# PicoKbd.net
KiCad netlist of a schematic drawn in EAGLE
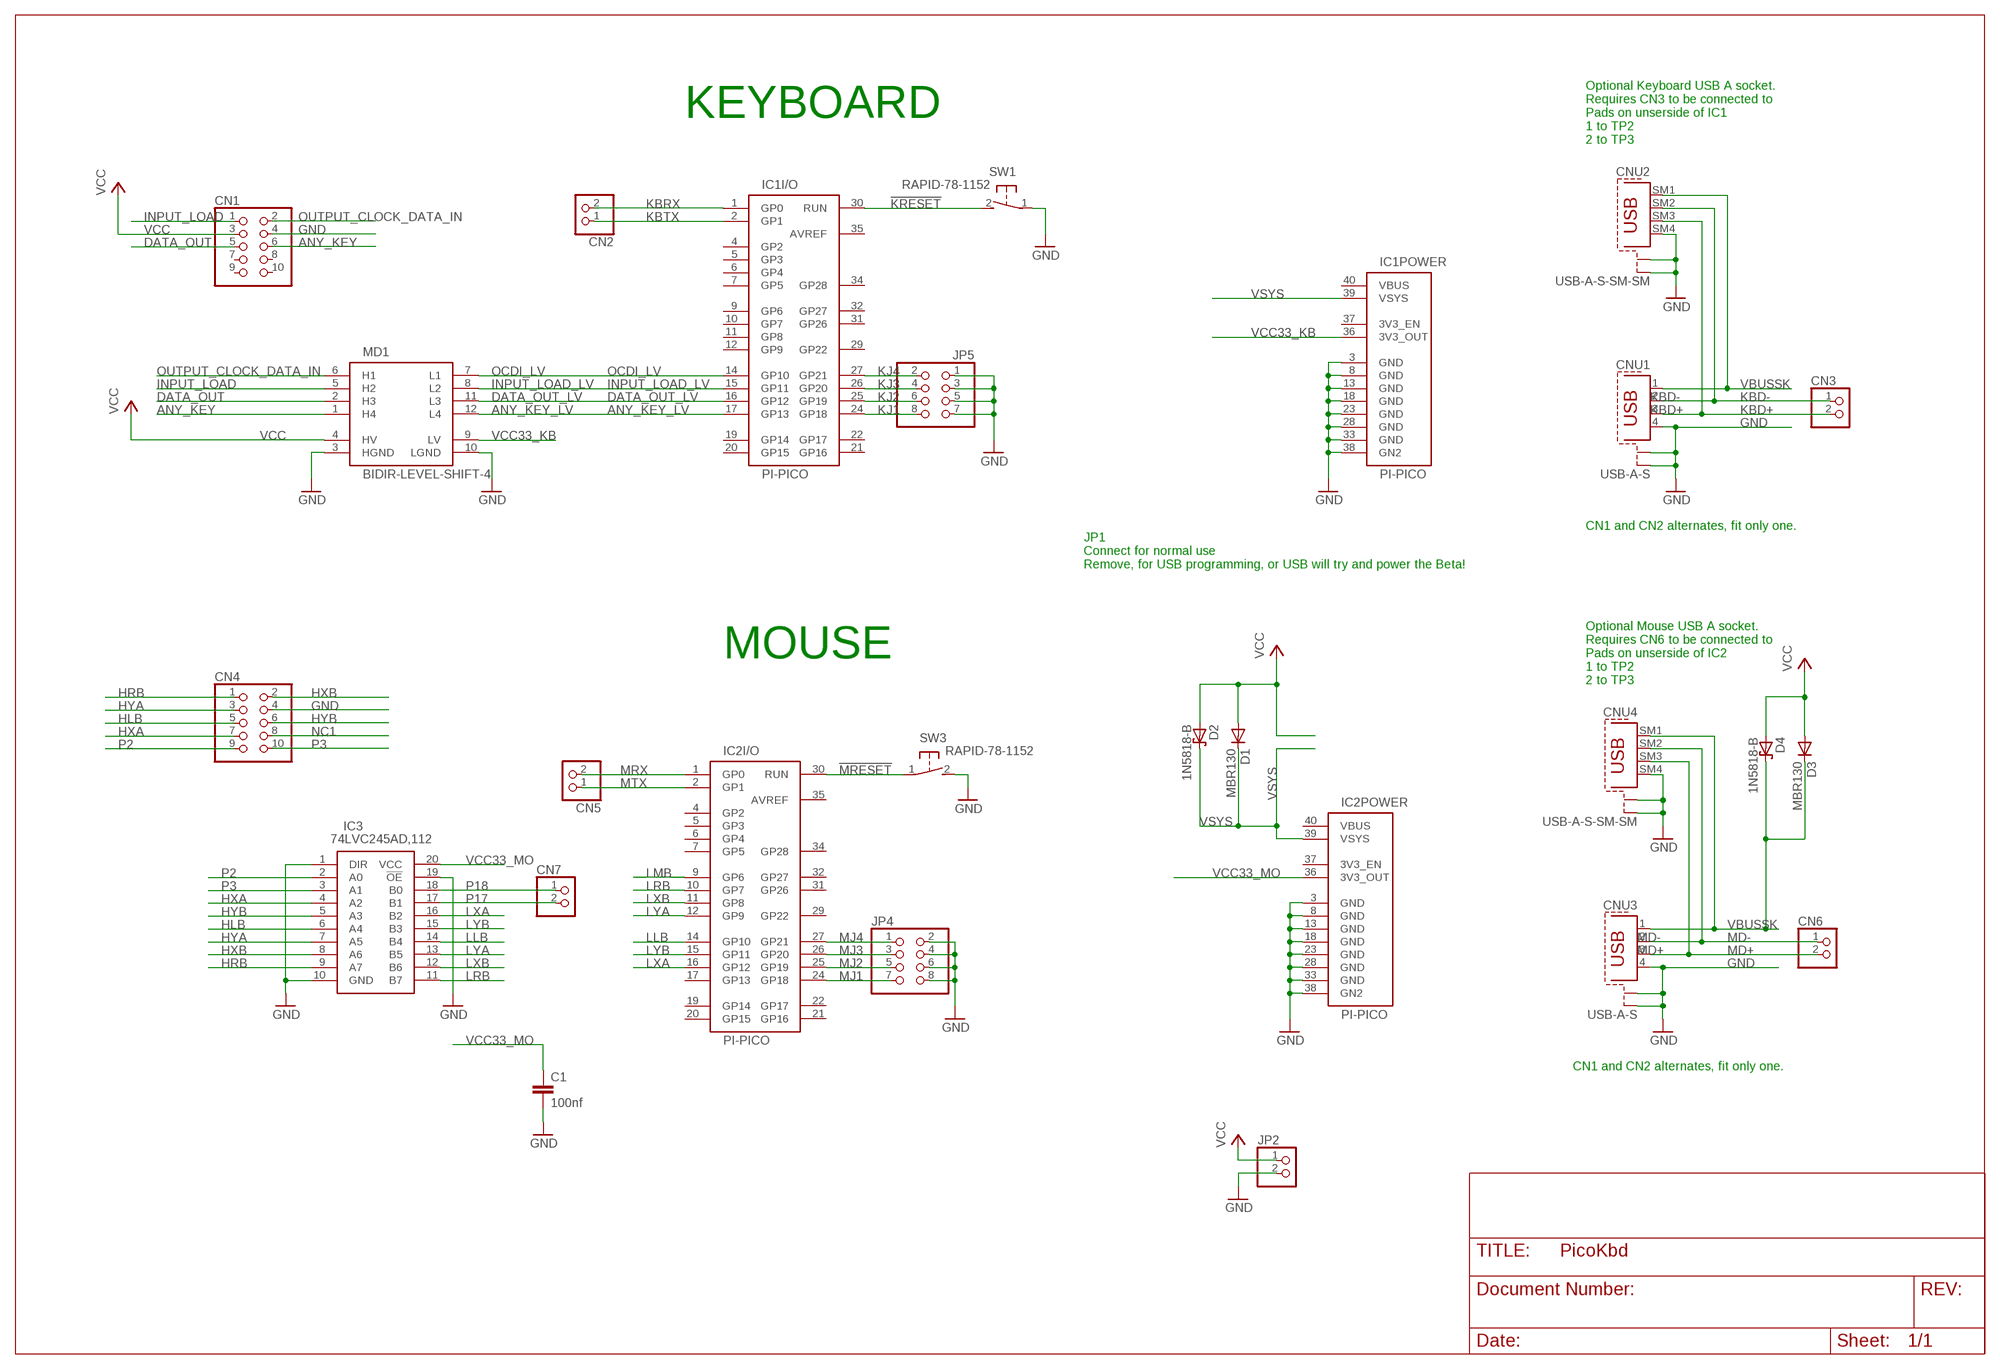
[diagram p0: schematic, sheet 1]

(export (version "E")
  (design (tool "Eeschema 10.0.6"))
  (components
    (comp (ref "C1")
      (value "100nf")
      (footprint "eagle-import:C025-025X050")
      (libsource (lib "eagle-import") (part "C-EU025-025X050"))
    )
    (comp (ref "CN1")
      (value "PINHD-2X5/90")
      (footprint "eagle-import:2X05_90")
      (libsource (lib "eagle-import") (part "PINHD-2X5/90"))
    )
    (comp (ref "CN2")
      (value "PINHD-1X2")
      (footprint "eagle-import:1X02")
      (libsource (lib "eagle-import") (part "PINHD-1X2"))
    )
    (comp (ref "CN3")
      (value "PINHD-1X2")
      (footprint "eagle-import:1X02")
      (libsource (lib "eagle-import") (part "PINHD-1X2"))
    )
    (comp (ref "CN4")
      (value "PINHD-2X5/90")
      (footprint "eagle-import:2X05_90")
      (libsource (lib "eagle-import") (part "PINHD-2X5/90"))
    )
    (comp (ref "CN5")
      (value "PINHD-1X2")
      (footprint "eagle-import:1X02")
      (libsource (lib "eagle-import") (part "PINHD-1X2"))
    )
    (comp (ref "CN6")
      (value "PINHD-1X2")
      (footprint "eagle-import:1X02")
      (libsource (lib "eagle-import") (part "PINHD-1X2"))
    )
    (comp (ref "CN7")
      (value "PINHD-1X2")
      (footprint "eagle-import:1X02")
      (libsource (lib "eagle-import") (part "PINHD-1X2"))
    )
    (comp (ref "CNU1")
      (value "USB-A-S")
      (footprint "eagle-import:USB-A-SHIELD-PTH")
      (libsource (lib "eagle-import") (part "USB-A-S"))
    )
    (comp (ref "CNU2")
      (value "USB-A-S-SM-SM")
      (footprint "eagle-import:USB-A-SHIELD-SM")
      (libsource (lib "eagle-import") (part "USB-A-S-SM-SM"))
    )
    (comp (ref "CNU3")
      (value "USB-A-S")
      (footprint "eagle-import:USB-A-SHIELD-PTH")
      (libsource (lib "eagle-import") (part "USB-A-S"))
    )
    (comp (ref "CNU4")
      (value "USB-A-S-SM-SM")
      (footprint "eagle-import:USB-A-SHIELD-SM")
      (libsource (lib "eagle-import") (part "USB-A-S-SM-SM"))
    )
    (comp (ref "D1")
      (value "MBR130")
      (footprint "eagle-import:SOD123")
      (libsource (lib "eagle-import") (part "MBR0520LT"))
    )
    (comp (ref "D2")
      (value "1N5818-B")
      (footprint "eagle-import:DO41-7.6")
      (libsource (lib "eagle-import") (part "1N5818-B"))
    )
    (comp (ref "D3")
      (value "MBR130")
      (footprint "eagle-import:SOD123")
      (libsource (lib "eagle-import") (part "MBR0520LT"))
    )
    (comp (ref "D4")
      (value "1N5818-B")
      (footprint "eagle-import:DO41-7.6")
      (libsource (lib "eagle-import") (part "1N5818-B"))
    )
    (comp (ref "IC1")
      (value "PI-PICO")
      (footprint "eagle-import:PI-PICO-MAIN")
      (libsource (lib "eagle-import") (part "PI-PICO"))
    )
    (comp (ref "IC2")
      (value "PI-PICO")
      (footprint "eagle-import:PI-PICO-MAIN")
      (libsource (lib "eagle-import") (part "PI-PICO"))
    )
    (comp (ref "IC3")
      (value "74LVC245AD,112")
      (footprint "eagle-import:SOIC127P1032X265-20N")
      (fields (field (name "RS_PART_NUMBER") "3800279P"))
      (libsource (lib "eagle-import") (part "74LVC245AD,112"))
    )
    (comp (ref "JP2")
      (value "PINHD-1X2/90")
      (footprint "eagle-import:1X02_90")
      (libsource (lib "eagle-import") (part "PINHD-1X2/90"))
    )
    (comp (ref "JP4")
      (value "PINHD-2X4")
      (footprint "eagle-import:2X04")
      (libsource (lib "eagle-import") (part "PINHD-2X4"))
    )
    (comp (ref "JP5")
      (value "PINHD-2X4")
      (footprint "eagle-import:2X04")
      (libsource (lib "eagle-import") (part "PINHD-2X4"))
    )
    (comp (ref "MD1")
      (value "BIDIR-LEVEL-SHIFT-4")
      (footprint "eagle-import:BIDIR-LEVEL-SHIFT")
      (libsource (lib "eagle-import") (part "BIDIR-LEVEL-SHIFT-4"))
    )
    (comp (ref "SW1")
      (value "RAPID-78-1152")
      (footprint "eagle-import:B3F-31XX")
      (libsource (lib "eagle-import") (part "RAPID-78-1152"))
    )
    (comp (ref "SW3")
      (value "RAPID-78-1152")
      (footprint "eagle-import:B3F-31XX")
      (libsource (lib "eagle-import") (part "RAPID-78-1152"))
    )
  )
  (nets
    (net (code "1") (name "/ANY_KEY") (class "Default")
      (node (ref "CN1") (pin "6") (pinfunction "6_6") (pintype "passive"))
      (node (ref "MD1") (pin "1") (pinfunction "H4_1") (pintype "passive"))
    )
    (net (code "2") (name "/ANY_KEY_LV") (class "Default")
      (node (ref "IC1") (pin "17") (pinfunction "GP13_17") (pintype "bidirectional"))
      (node (ref "MD1") (pin "12") (pinfunction "L4_12") (pintype "passive"))
    )
    (net (code "3") (name "/DATA_OUT") (class "Default")
      (node (ref "CN1") (pin "5") (pinfunction "5_5") (pintype "passive"))
      (node (ref "MD1") (pin "2") (pinfunction "H3_2") (pintype "passive"))
    )
    (net (code "4") (name "/DATA_OUT_LV") (class "Default")
      (node (ref "IC1") (pin "16") (pinfunction "GP12_16") (pintype "bidirectional"))
      (node (ref "MD1") (pin "11") (pinfunction "L3_11") (pintype "passive"))
    )
    (net (code "5") (name "/HLB") (class "Default")
      (node (ref "CN4") (pin "5") (pinfunction "5_5") (pintype "passive"))
      (node (ref "IC3") (pin "6") (pinfunction "A4_6") (pintype "bidirectional"))
    )
    (net (code "6") (name "/HRB") (class "Default")
      (node (ref "CN4") (pin "1") (pinfunction "1_1") (pintype "passive"))
      (node (ref "IC3") (pin "9") (pinfunction "A7_9") (pintype "bidirectional"))
    )
    (net (code "7") (name "/HXA") (class "Default")
      (node (ref "CN4") (pin "7") (pinfunction "7_7") (pintype "passive"))
      (node (ref "IC3") (pin "4") (pinfunction "A2_4") (pintype "bidirectional"))
    )
    (net (code "8") (name "/HXB") (class "Default")
      (node (ref "CN4") (pin "2") (pinfunction "2_2") (pintype "passive"))
      (node (ref "IC3") (pin "8") (pinfunction "A6_8") (pintype "bidirectional"))
    )
    (net (code "9") (name "/HYA") (class "Default")
      (node (ref "CN4") (pin "3") (pinfunction "3_3") (pintype "passive"))
      (node (ref "IC3") (pin "7") (pinfunction "A5_7") (pintype "bidirectional"))
    )
    (net (code "10") (name "/HYB") (class "Default")
      (node (ref "CN4") (pin "6") (pinfunction "6_6") (pintype "passive"))
      (node (ref "IC3") (pin "5") (pinfunction "A3_5") (pintype "bidirectional"))
    )
    (net (code "11") (name "/INPUT_LOAD") (class "Default")
      (node (ref "CN1") (pin "1") (pinfunction "1_1") (pintype "passive"))
      (node (ref "MD1") (pin "5") (pinfunction "H2_5") (pintype "passive"))
    )
    (net (code "12") (name "/INPUT_LOAD_LV") (class "Default")
      (node (ref "IC1") (pin "15") (pinfunction "GP11_15") (pintype "bidirectional"))
      (node (ref "MD1") (pin "8") (pinfunction "L2_8") (pintype "passive"))
    )
    (net (code "13") (name "/KBD+") (class "Default")
      (node (ref "CN3") (pin "2") (pinfunction "2_2") (pintype "passive"))
      (node (ref "CNU1") (pin "3") (pinfunction "3_3") (pintype "passive"))
      (node (ref "CNU2") (pin "SM3") (pinfunction "3_SM3") (pintype "passive"))
    )
    (net (code "14") (name "/KBD-") (class "Default")
      (node (ref "CN3") (pin "1") (pinfunction "1_1") (pintype "passive"))
      (node (ref "CNU1") (pin "2") (pinfunction "2_2") (pintype "passive"))
      (node (ref "CNU2") (pin "SM2") (pinfunction "2_SM2") (pintype "passive"))
    )
    (net (code "15") (name "/KBRX") (class "Default")
      (node (ref "CN2") (pin "2") (pinfunction "2_2") (pintype "passive"))
      (node (ref "IC1") (pin "1") (pinfunction "GP0_1") (pintype "bidirectional"))
    )
    (net (code "16") (name "/KBTX") (class "Default")
      (node (ref "CN2") (pin "1") (pinfunction "1_1") (pintype "passive"))
      (node (ref "IC1") (pin "2") (pinfunction "GP1_2") (pintype "bidirectional"))
    )
    (net (code "17") (name "/KJ1") (class "Default")
      (node (ref "IC1") (pin "24") (pinfunction "GP18_24") (pintype "bidirectional"))
      (node (ref "JP5") (pin "8") (pinfunction "8_8") (pintype "passive"))
    )
    (net (code "18") (name "/KJ2") (class "Default")
      (node (ref "IC1") (pin "25") (pinfunction "GP19_25") (pintype "bidirectional"))
      (node (ref "JP5") (pin "6") (pinfunction "6_6") (pintype "passive"))
    )
    (net (code "19") (name "/KJ3") (class "Default")
      (node (ref "IC1") (pin "26") (pinfunction "GP20_26") (pintype "bidirectional"))
      (node (ref "JP5") (pin "4") (pinfunction "4_4") (pintype "passive"))
    )
    (net (code "20") (name "/KJ4") (class "Default")
      (node (ref "IC1") (pin "27") (pinfunction "GP21_27") (pintype "bidirectional"))
      (node (ref "JP5") (pin "2") (pinfunction "2_2") (pintype "passive"))
    )
    (net (code "21") (name "/LLB") (class "Default")
      (node (ref "IC2") (pin "14") (pinfunction "GP10_14") (pintype "bidirectional"))
      (node (ref "IC3") (pin "14") (pinfunction "B4_14") (pintype "bidirectional"))
    )
    (net (code "22") (name "/LMB") (class "Default")
      (node (ref "IC2") (pin "9") (pinfunction "GP6_9") (pintype "bidirectional"))
    )
    (net (code "23") (name "/LRB") (class "Default")
      (node (ref "IC2") (pin "10") (pinfunction "GP7_10") (pintype "bidirectional"))
      (node (ref "IC3") (pin "11") (pinfunction "B7_11") (pintype "bidirectional"))
    )
    (net (code "24") (name "/LXA") (class "Default")
      (node (ref "IC2") (pin "16") (pinfunction "GP12_16") (pintype "bidirectional"))
      (node (ref "IC3") (pin "16") (pinfunction "B2_16") (pintype "bidirectional"))
    )
    (net (code "25") (name "/LXB") (class "Default")
      (node (ref "IC2") (pin "11") (pinfunction "GP8_11") (pintype "bidirectional"))
      (node (ref "IC3") (pin "12") (pinfunction "B6_12") (pintype "bidirectional"))
    )
    (net (code "26") (name "/LYA") (class "Default")
      (node (ref "IC2") (pin "12") (pinfunction "GP9_12") (pintype "bidirectional"))
      (node (ref "IC3") (pin "13") (pinfunction "B5_13") (pintype "bidirectional"))
    )
    (net (code "27") (name "/LYB") (class "Default")
      (node (ref "IC2") (pin "15") (pinfunction "GP11_15") (pintype "bidirectional"))
      (node (ref "IC3") (pin "15") (pinfunction "B3_15") (pintype "bidirectional"))
    )
    (net (code "28") (name "/MD+") (class "Default")
      (node (ref "CN6") (pin "2") (pinfunction "2_2") (pintype "passive"))
      (node (ref "CNU3") (pin "3") (pinfunction "3_3") (pintype "passive"))
      (node (ref "CNU4") (pin "SM3") (pinfunction "3_SM3") (pintype "passive"))
    )
    (net (code "29") (name "/MD-") (class "Default")
      (node (ref "CN6") (pin "1") (pinfunction "1_1") (pintype "passive"))
      (node (ref "CNU3") (pin "2") (pinfunction "2_2") (pintype "passive"))
      (node (ref "CNU4") (pin "SM2") (pinfunction "2_SM2") (pintype "passive"))
    )
    (net (code "30") (name "/MJ1") (class "Default")
      (node (ref "IC2") (pin "24") (pinfunction "GP18_24") (pintype "bidirectional"))
      (node (ref "JP4") (pin "7") (pinfunction "7_7") (pintype "passive"))
    )
    (net (code "31") (name "/MJ2") (class "Default")
      (node (ref "IC2") (pin "25") (pinfunction "GP19_25") (pintype "bidirectional"))
      (node (ref "JP4") (pin "5") (pinfunction "5_5") (pintype "passive"))
    )
    (net (code "32") (name "/MJ3") (class "Default")
      (node (ref "IC2") (pin "26") (pinfunction "GP20_26") (pintype "bidirectional"))
      (node (ref "JP4") (pin "3") (pinfunction "3_3") (pintype "passive"))
    )
    (net (code "33") (name "/MJ4") (class "Default")
      (node (ref "IC2") (pin "27") (pinfunction "GP21_27") (pintype "bidirectional"))
      (node (ref "JP4") (pin "1") (pinfunction "1_1") (pintype "passive"))
    )
    (net (code "34") (name "/MRX") (class "Default")
      (node (ref "CN5") (pin "2") (pinfunction "2_2") (pintype "passive"))
      (node (ref "IC2") (pin "1") (pinfunction "GP0_1") (pintype "bidirectional"))
    )
    (net (code "35") (name "/MTX") (class "Default")
      (node (ref "CN5") (pin "1") (pinfunction "1_1") (pintype "passive"))
      (node (ref "IC2") (pin "2") (pinfunction "GP1_2") (pintype "bidirectional"))
    )
    (net (code "36") (name "/NC1") (class "Default")
      (node (ref "CN4") (pin "8") (pinfunction "8_8") (pintype "passive"))
    )
    (net (code "37") (name "/OCDI_LV") (class "Default")
      (node (ref "IC1") (pin "14") (pinfunction "GP10_14") (pintype "bidirectional"))
      (node (ref "MD1") (pin "7") (pinfunction "L1_7") (pintype "passive"))
    )
    (net (code "38") (name "/OUTPUT_CLOCK_DATA_IN") (class "Default")
      (node (ref "CN1") (pin "2") (pinfunction "2_2") (pintype "passive"))
      (node (ref "MD1") (pin "6") (pinfunction "H1_6") (pintype "passive"))
    )
    (net (code "39") (name "/P2") (class "Default")
      (node (ref "CN4") (pin "9") (pinfunction "9_9") (pintype "passive"))
      (node (ref "IC3") (pin "2") (pinfunction "A0_2") (pintype "bidirectional"))
    )
    (net (code "40") (name "/P3") (class "Default")
      (node (ref "CN4") (pin "10") (pinfunction "10_10") (pintype "passive"))
      (node (ref "IC3") (pin "3") (pinfunction "A1_3") (pintype "bidirectional"))
    )
    (net (code "41") (name "/P17") (class "Default")
      (node (ref "CN7") (pin "2") (pinfunction "2_2") (pintype "passive"))
      (node (ref "IC3") (pin "17") (pinfunction "B1_17") (pintype "bidirectional"))
    )
    (net (code "42") (name "/P18") (class "Default")
      (node (ref "CN7") (pin "1") (pinfunction "1_1") (pintype "passive"))
      (node (ref "IC3") (pin "18") (pinfunction "B0_18") (pintype "bidirectional"))
    )
    (net (code "43") (name "/VBUSSK") (class "Default")
      (node (ref "CNU1") (pin "1") (pinfunction "1_1") (pintype "passive"))
      (node (ref "CNU2") (pin "SM1") (pinfunction "1_SM1") (pintype "passive"))
      (node (ref "CNU3") (pin "1") (pinfunction "1_1") (pintype "passive"))
      (node (ref "CNU4") (pin "SM1") (pinfunction "1_SM1") (pintype "passive"))
      (node (ref "D3") (pin "C") (pinfunction "C_C") (pintype "passive"))
      (node (ref "D4") (pin "C") (pinfunction "C_C") (pintype "passive"))
    )
    (net (code "44") (name "/VCC33_KB") (class "Default")
      (node (ref "IC1") (pin "36") (pinfunction "3V3_OUT_36") (pintype "bidirectional"))
      (node (ref "MD1") (pin "9") (pinfunction "LV_9") (pintype "power_in"))
    )
    (net (code "45") (name "/VCC33_MO") (class "Default")
      (node (ref "C1") (pin "1") (pinfunction "1_1") (pintype "passive"))
      (node (ref "IC2") (pin "36") (pinfunction "3V3_OUT_36") (pintype "bidirectional"))
      (node (ref "IC3") (pin "20") (pinfunction "VCC_20") (pintype "bidirectional"))
    )
    (net (code "46") (name "/VSYS") (class "Default")
      (node (ref "D1") (pin "C") (pinfunction "C_C") (pintype "passive"))
      (node (ref "D2") (pin "C") (pinfunction "C_C") (pintype "passive"))
      (node (ref "IC1") (pin "39") (pinfunction "VSYS_39") (pintype "bidirectional"))
      (node (ref "IC2") (pin "39") (pinfunction "VSYS_39") (pintype "bidirectional"))
    )
    (net (code "47") (name "/~{KRESET}") (class "Default")
      (node (ref "IC1") (pin "30") (pinfunction "RUN_30") (pintype "bidirectional"))
      (node (ref "SW1") (pin "2") (pinfunction "S_2") (pintype "passive"))
    )
    (net (code "48") (name "/~{MRESET}") (class "Default")
      (node (ref "IC2") (pin "30") (pinfunction "RUN_30") (pintype "bidirectional"))
      (node (ref "SW3") (pin "1") (pinfunction "P_1") (pintype "passive"))
    )
    (net (code "49") (name "GND") (class "Default")
      (node (ref "C1") (pin "2") (pinfunction "2_2") (pintype "passive"))
      (node (ref "CN1") (pin "4") (pinfunction "4_4") (pintype "passive"))
      (node (ref "CN4") (pin "4") (pinfunction "4_4") (pintype "passive"))
      (node (ref "CNU1") (pin "4") (pinfunction "4_4") (pintype "passive"))
      (node (ref "CNU1") (pin "S1") (pinfunction "S1_S1") (pintype "passive"))
      (node (ref "CNU1") (pin "S2") (pinfunction "S2_S2") (pintype "passive"))
      (node (ref "CNU2") (pin "S1") (pinfunction "S1_S1") (pintype "passive"))
      (node (ref "CNU2") (pin "S2") (pinfunction "S2_S2") (pintype "passive"))
      (node (ref "CNU2") (pin "SM4") (pinfunction "4_SM4") (pintype "passive"))
      (node (ref "CNU3") (pin "4") (pinfunction "4_4") (pintype "passive"))
      (node (ref "CNU3") (pin "S1") (pinfunction "S1_S1") (pintype "passive"))
      (node (ref "CNU3") (pin "S2") (pinfunction "S2_S2") (pintype "passive"))
      (node (ref "CNU4") (pin "S1") (pinfunction "S1_S1") (pintype "passive"))
      (node (ref "CNU4") (pin "S2") (pinfunction "S2_S2") (pintype "passive"))
      (node (ref "CNU4") (pin "SM4") (pinfunction "4_SM4") (pintype "passive"))
      (node (ref "IC1") (pin "13") (pinfunction "GND_13") (pintype "bidirectional"))
      (node (ref "IC1") (pin "18") (pinfunction "GND_18") (pintype "bidirectional"))
      (node (ref "IC1") (pin "23") (pinfunction "GND_23") (pintype "bidirectional"))
      (node (ref "IC1") (pin "28") (pinfunction "GND_28") (pintype "bidirectional"))
      (node (ref "IC1") (pin "3") (pinfunction "GND_3") (pintype "bidirectional"))
      (node (ref "IC1") (pin "33") (pinfunction "GND_33") (pintype "bidirectional"))
      (node (ref "IC1") (pin "38") (pinfunction "GN2_38") (pintype "bidirectional"))
      (node (ref "IC1") (pin "8") (pinfunction "GND_8") (pintype "bidirectional"))
      (node (ref "IC2") (pin "13") (pinfunction "GND_13") (pintype "bidirectional"))
      (node (ref "IC2") (pin "18") (pinfunction "GND_18") (pintype "bidirectional"))
      (node (ref "IC2") (pin "23") (pinfunction "GND_23") (pintype "bidirectional"))
      (node (ref "IC2") (pin "28") (pinfunction "GND_28") (pintype "bidirectional"))
      (node (ref "IC2") (pin "3") (pinfunction "GND_3") (pintype "bidirectional"))
      (node (ref "IC2") (pin "33") (pinfunction "GND_33") (pintype "bidirectional"))
      (node (ref "IC2") (pin "38") (pinfunction "GN2_38") (pintype "bidirectional"))
      (node (ref "IC2") (pin "8") (pinfunction "GND_8") (pintype "bidirectional"))
      (node (ref "IC3") (pin "1") (pinfunction "DIR_1") (pintype "bidirectional"))
      (node (ref "IC3") (pin "10") (pinfunction "GND_10") (pintype "bidirectional"))
      (node (ref "IC3") (pin "19") (pinfunction "~{OE}_19") (pintype "bidirectional"))
      (node (ref "JP2") (pin "2") (pinfunction "2_2") (pintype "passive"))
      (node (ref "JP4") (pin "2") (pinfunction "2_2") (pintype "passive"))
      (node (ref "JP4") (pin "4") (pinfunction "4_4") (pintype "passive"))
      (node (ref "JP4") (pin "6") (pinfunction "6_6") (pintype "passive"))
      (node (ref "JP4") (pin "8") (pinfunction "8_8") (pintype "passive"))
      (node (ref "JP5") (pin "1") (pinfunction "1_1") (pintype "passive"))
      (node (ref "JP5") (pin "3") (pinfunction "3_3") (pintype "passive"))
      (node (ref "JP5") (pin "5") (pinfunction "5_5") (pintype "passive"))
      (node (ref "JP5") (pin "7") (pinfunction "7_7") (pintype "passive"))
      (node (ref "MD1") (pin "10") (pinfunction "LGND_10") (pintype "bidirectional"))
      (node (ref "MD1") (pin "3") (pinfunction "HGND_3") (pintype "bidirectional"))
      (node (ref "SW1") (pin "1") (pinfunction "P_1") (pintype "passive"))
      (node (ref "SW3") (pin "2") (pinfunction "S_2") (pintype "passive"))
    )
    (net (code "50") (name "VCC") (class "Default")
      (node (ref "CN1") (pin "3") (pinfunction "3_3") (pintype "passive"))
      (node (ref "D1") (pin "A") (pinfunction "A_A") (pintype "passive"))
      (node (ref "D2") (pin "A") (pinfunction "A_A") (pintype "passive"))
      (node (ref "D3") (pin "A") (pinfunction "A_A") (pintype "passive"))
      (node (ref "D4") (pin "A") (pinfunction "A_A") (pintype "passive"))
      (node (ref "JP2") (pin "1") (pinfunction "1_1") (pintype "passive"))
      (node (ref "MD1") (pin "4") (pinfunction "HV_4") (pintype "power_in"))
    )
    (net (code "51") (name "unconnected-(CN1-Pad7)") (class "Default")
      (node (ref "CN1") (pin "7") (pinfunction "7_7") (pintype "passive"))
    )
    (net (code "52") (name "unconnected-(CN1-Pad8)") (class "Default")
      (node (ref "CN1") (pin "8") (pinfunction "8_8") (pintype "passive"))
    )
    (net (code "53") (name "unconnected-(CN1-Pad9)") (class "Default")
      (node (ref "CN1") (pin "9") (pinfunction "9_9") (pintype "passive"))
    )
    (net (code "54") (name "unconnected-(CN1-Pad10)") (class "Default")
      (node (ref "CN1") (pin "10") (pinfunction "10_10") (pintype "passive"))
    )
    (net (code "55") (name "unconnected-(IC1A-AVREF-Pad35)") (class "Default")
      (node (ref "IC1") (pin "35") (pinfunction "AVREF_35") (pintype "bidirectional"))
    )
    (net (code "56") (name "unconnected-(IC1A-GP2-Pad4)") (class "Default")
      (node (ref "IC1") (pin "4") (pinfunction "GP2_4") (pintype "bidirectional"))
    )
    (net (code "57") (name "unconnected-(IC1A-GP3-Pad5)") (class "Default")
      (node (ref "IC1") (pin "5") (pinfunction "GP3_5") (pintype "bidirectional"))
    )
    (net (code "58") (name "unconnected-(IC1A-GP4-Pad6)") (class "Default")
      (node (ref "IC1") (pin "6") (pinfunction "GP4_6") (pintype "bidirectional"))
    )
    (net (code "59") (name "unconnected-(IC1A-GP5-Pad7)") (class "Default")
      (node (ref "IC1") (pin "7") (pinfunction "GP5_7") (pintype "bidirectional"))
    )
    (net (code "60") (name "unconnected-(IC1A-GP6-Pad9)") (class "Default")
      (node (ref "IC1") (pin "9") (pinfunction "GP6_9") (pintype "bidirectional"))
    )
    (net (code "61") (name "unconnected-(IC1A-GP7-Pad10)") (class "Default")
      (node (ref "IC1") (pin "10") (pinfunction "GP7_10") (pintype "bidirectional"))
    )
    (net (code "62") (name "unconnected-(IC1A-GP8-Pad11)") (class "Default")
      (node (ref "IC1") (pin "11") (pinfunction "GP8_11") (pintype "bidirectional"))
    )
    (net (code "63") (name "unconnected-(IC1A-GP9-Pad12)") (class "Default")
      (node (ref "IC1") (pin "12") (pinfunction "GP9_12") (pintype "bidirectional"))
    )
    (net (code "64") (name "unconnected-(IC1A-GP14-Pad19)") (class "Default")
      (node (ref "IC1") (pin "19") (pinfunction "GP14_19") (pintype "bidirectional"))
    )
    (net (code "65") (name "unconnected-(IC1A-GP15-Pad20)") (class "Default")
      (node (ref "IC1") (pin "20") (pinfunction "GP15_20") (pintype "bidirectional"))
    )
    (net (code "66") (name "unconnected-(IC1A-GP16-Pad21)") (class "Default")
      (node (ref "IC1") (pin "21") (pinfunction "GP16_21") (pintype "bidirectional"))
    )
    (net (code "67") (name "unconnected-(IC1A-GP17-Pad22)") (class "Default")
      (node (ref "IC1") (pin "22") (pinfunction "GP17_22") (pintype "bidirectional"))
    )
    (net (code "68") (name "unconnected-(IC1A-GP22-Pad29)") (class "Default")
      (node (ref "IC1") (pin "29") (pinfunction "GP22_29") (pintype "bidirectional"))
    )
    (net (code "69") (name "unconnected-(IC1A-GP26-Pad31)") (class "Default")
      (node (ref "IC1") (pin "31") (pinfunction "GP26_31") (pintype "bidirectional"))
    )
    (net (code "70") (name "unconnected-(IC1A-GP27-Pad32)") (class "Default")
      (node (ref "IC1") (pin "32") (pinfunction "GP27_32") (pintype "bidirectional"))
    )
    (net (code "71") (name "unconnected-(IC1A-GP28-Pad34)") (class "Default")
      (node (ref "IC1") (pin "34") (pinfunction "GP28_34") (pintype "bidirectional"))
    )
    (net (code "72") (name "unconnected-(IC1B-3V3_EN-Pad37)") (class "Default")
      (node (ref "IC1") (pin "37") (pinfunction "3V3_EN_37") (pintype "bidirectional"))
    )
    (net (code "73") (name "unconnected-(IC1B-VBUS-Pad40)") (class "Default")
      (node (ref "IC1") (pin "40") (pinfunction "VBUS_40") (pintype "bidirectional"))
    )
    (net (code "74") (name "unconnected-(IC2A-AVREF-Pad35)") (class "Default")
      (node (ref "IC2") (pin "35") (pinfunction "AVREF_35") (pintype "bidirectional"))
    )
    (net (code "75") (name "unconnected-(IC2A-GP2-Pad4)") (class "Default")
      (node (ref "IC2") (pin "4") (pinfunction "GP2_4") (pintype "bidirectional"))
    )
    (net (code "76") (name "unconnected-(IC2A-GP3-Pad5)") (class "Default")
      (node (ref "IC2") (pin "5") (pinfunction "GP3_5") (pintype "bidirectional"))
    )
    (net (code "77") (name "unconnected-(IC2A-GP4-Pad6)") (class "Default")
      (node (ref "IC2") (pin "6") (pinfunction "GP4_6") (pintype "bidirectional"))
    )
    (net (code "78") (name "unconnected-(IC2A-GP5-Pad7)") (class "Default")
      (node (ref "IC2") (pin "7") (pinfunction "GP5_7") (pintype "bidirectional"))
    )
    (net (code "79") (name "unconnected-(IC2A-GP13-Pad17)") (class "Default")
      (node (ref "IC2") (pin "17") (pinfunction "GP13_17") (pintype "bidirectional"))
    )
    (net (code "80") (name "unconnected-(IC2A-GP14-Pad19)") (class "Default")
      (node (ref "IC2") (pin "19") (pinfunction "GP14_19") (pintype "bidirectional"))
    )
    (net (code "81") (name "unconnected-(IC2A-GP15-Pad20)") (class "Default")
      (node (ref "IC2") (pin "20") (pinfunction "GP15_20") (pintype "bidirectional"))
    )
    (net (code "82") (name "unconnected-(IC2A-GP16-Pad21)") (class "Default")
      (node (ref "IC2") (pin "21") (pinfunction "GP16_21") (pintype "bidirectional"))
    )
    (net (code "83") (name "unconnected-(IC2A-GP17-Pad22)") (class "Default")
      (node (ref "IC2") (pin "22") (pinfunction "GP17_22") (pintype "bidirectional"))
    )
    (net (code "84") (name "unconnected-(IC2A-GP22-Pad29)") (class "Default")
      (node (ref "IC2") (pin "29") (pinfunction "GP22_29") (pintype "bidirectional"))
    )
    (net (code "85") (name "unconnected-(IC2A-GP26-Pad31)") (class "Default")
      (node (ref "IC2") (pin "31") (pinfunction "GP26_31") (pintype "bidirectional"))
    )
    (net (code "86") (name "unconnected-(IC2A-GP27-Pad32)") (class "Default")
      (node (ref "IC2") (pin "32") (pinfunction "GP27_32") (pintype "bidirectional"))
    )
    (net (code "87") (name "unconnected-(IC2A-GP28-Pad34)") (class "Default")
      (node (ref "IC2") (pin "34") (pinfunction "GP28_34") (pintype "bidirectional"))
    )
    (net (code "88") (name "unconnected-(IC2B-3V3_EN-Pad37)") (class "Default")
      (node (ref "IC2") (pin "37") (pinfunction "3V3_EN_37") (pintype "bidirectional"))
    )
    (net (code "89") (name "unconnected-(IC2B-VBUS-Pad40)") (class "Default")
      (node (ref "IC2") (pin "40") (pinfunction "VBUS_40") (pintype "bidirectional"))
    )
  )
)
